# ASL1003.net
KiCad netlist of a schematic drawn in EAGLE
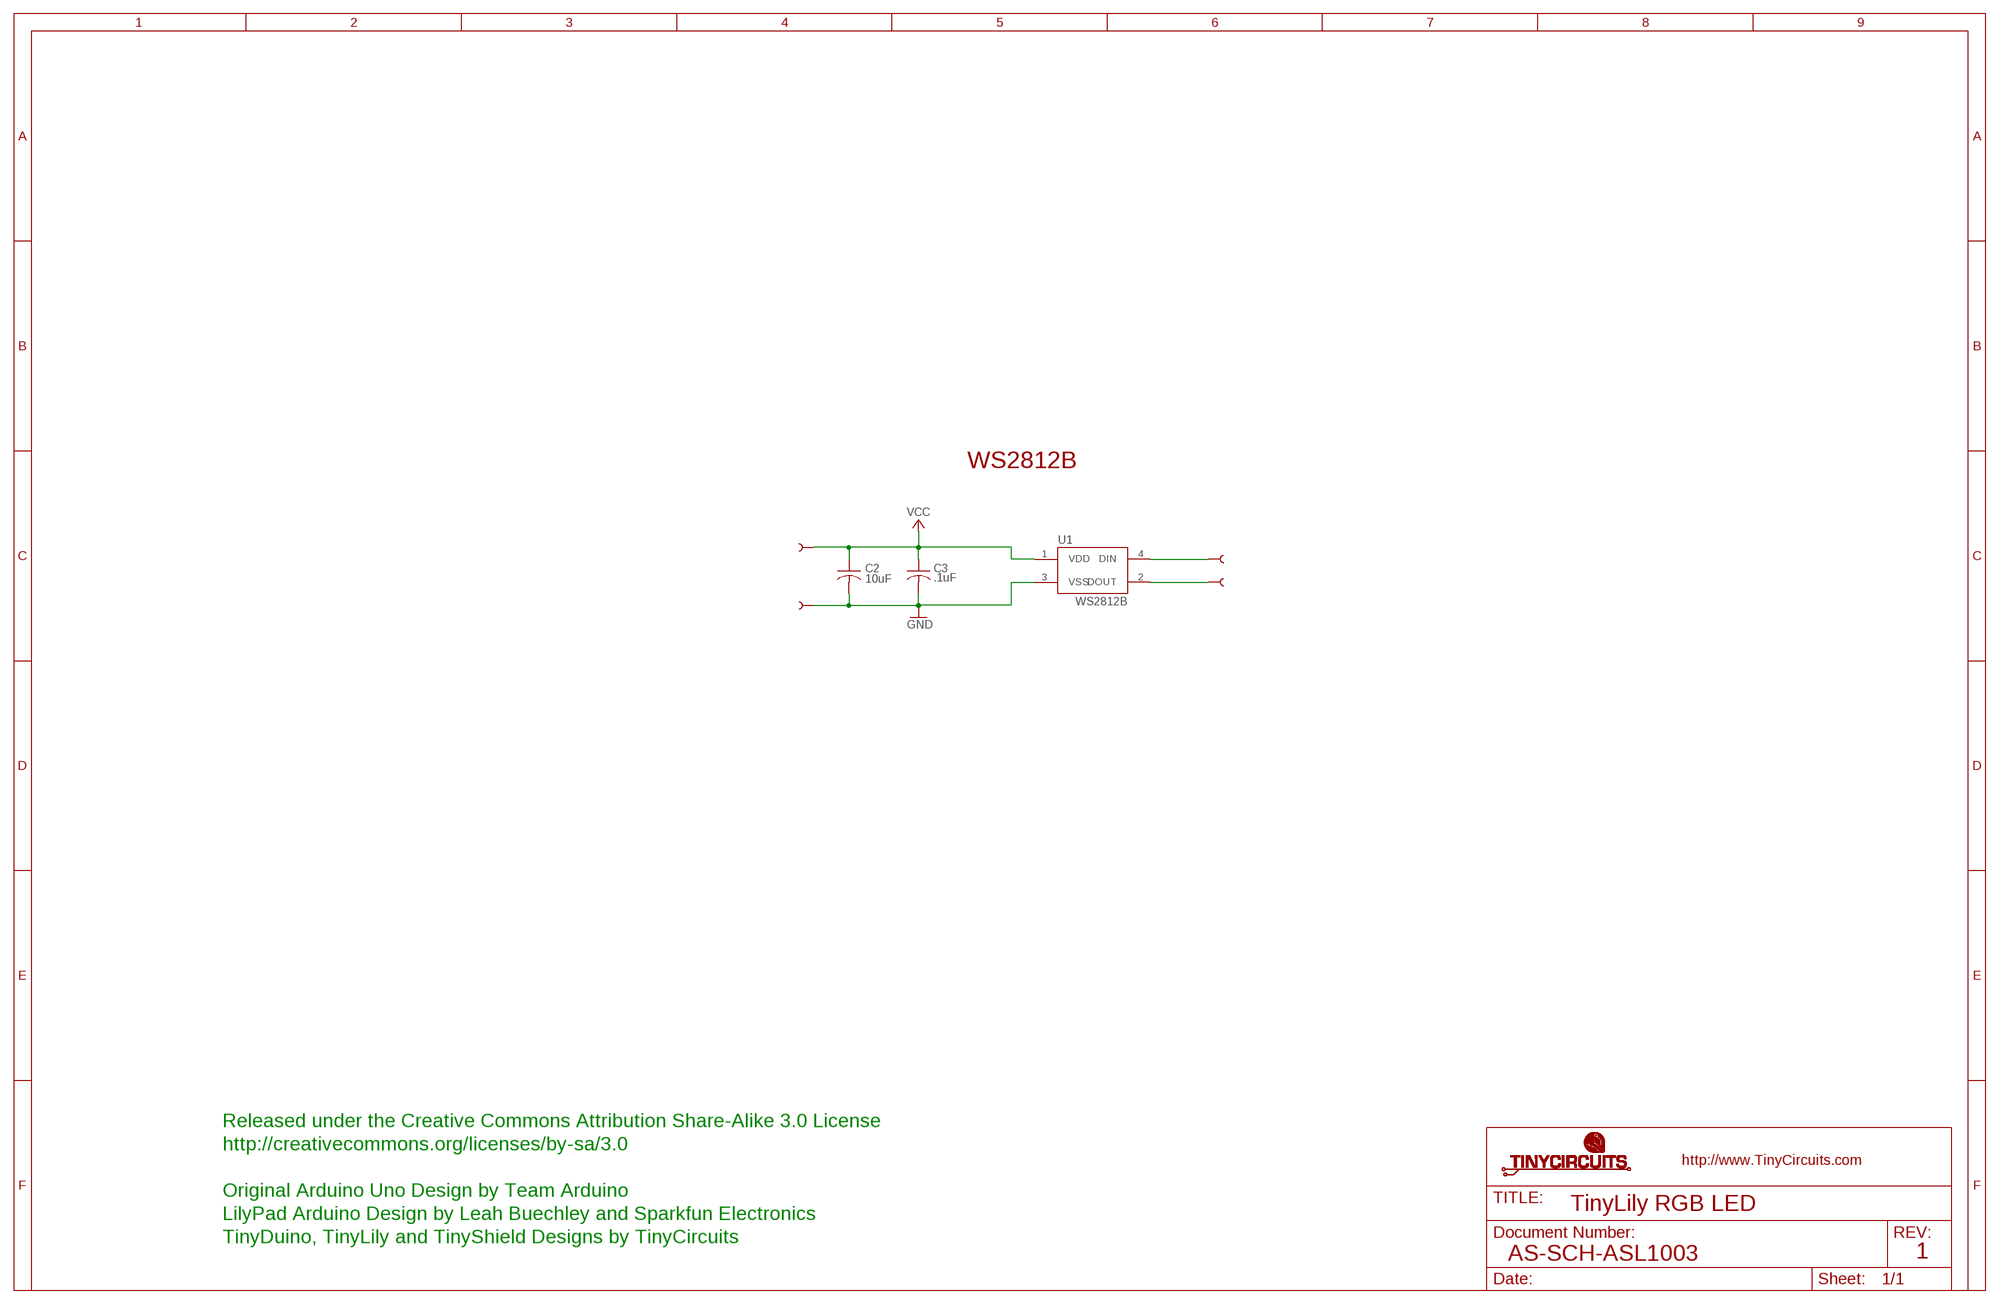
[diagram p0: schematic, sheet 1]

(export (version "E")
  (design (tool "Eeschema 10.0.6"))
  (components
    (comp (ref "C2")
      (value "10uF")
      (footprint "eagle-import:C0603")
      (fields (field (name "PARTNO") "AS-ITM-00002") (field (name "PARTNO_1") "AS-ITM-00002"))
      (libsource (lib "eagle-import") (part "AS-ITM-00002"))
    )
    (comp (ref "C3")
      (value ".1uF")
      (footprint "eagle-import:C0402")
      (fields (field (name "PARTNO") "AS-ITM-00008") (field (name "PARTNO_1") "AS-ITM-00008"))
      (libsource (lib "eagle-import") (part "AS-ITM-00008"))
    )
    (comp (ref "U$3")
      (value "SEWTABTH_10MM")
      (footprint "eagle-import:SEWTAP_TH_10MM")
      (libsource (lib "eagle-import") (part "SEWTABTH_10MM"))
    )
    (comp (ref "U$7")
      (value "SEWTABTH_10MM")
      (footprint "eagle-import:SEWTAP_TH_10MM")
      (libsource (lib "eagle-import") (part "SEWTABTH_10MM"))
    )
    (comp (ref "U$8")
      (value "SEWTABTH_10MM")
      (footprint "eagle-import:SEWTAP_TH_10MM")
      (libsource (lib "eagle-import") (part "SEWTABTH_10MM"))
    )
    (comp (ref "U$9")
      (value "SEWTABTH_10MM")
      (footprint "eagle-import:SEWTAP_TH_10MM")
      (libsource (lib "eagle-import") (part "SEWTABTH_10MM"))
    )
    (comp (ref "U1")
      (value "WS2812B")
      (footprint "eagle-import:WS2812B")
      (fields (field (name "PARTNO") "AS-ITM-00221"))
      (libsource (lib "eagle-import") (part "AS-ITM-00221"))
    )
  )
  (nets
    (net (code "1") (name "GND") (class "Default")
      (node (ref "C2") (pin "2") (pinfunction "2_2") (pintype "passive"))
      (node (ref "C3") (pin "2") (pinfunction "2_2") (pintype "passive"))
      (node (ref "U$7") (pin "1") (pinfunction "1_1") (pintype "bidirectional"))
      (node (ref "U1") (pin "3") (pinfunction "VSS_3") (pintype "bidirectional"))
    )
    (net (code "2") (name "Net-(U1-DIN)") (class "Default")
      (node (ref "U$3") (pin "1") (pinfunction "1_1") (pintype "bidirectional"))
      (node (ref "U1") (pin "4") (pinfunction "DIN_4") (pintype "bidirectional"))
    )
    (net (code "3") (name "Net-(U1-DOUT)") (class "Default")
      (node (ref "U$9") (pin "1") (pinfunction "1_1") (pintype "bidirectional"))
      (node (ref "U1") (pin "2") (pinfunction "DOUT_2") (pintype "bidirectional"))
    )
    (net (code "4") (name "VCC") (class "Default")
      (node (ref "C2") (pin "1") (pinfunction "1_1") (pintype "passive"))
      (node (ref "C3") (pin "1") (pinfunction "1_1") (pintype "passive"))
      (node (ref "U$8") (pin "1") (pinfunction "1_1") (pintype "bidirectional"))
      (node (ref "U1") (pin "1") (pinfunction "VDD_1") (pintype "bidirectional"))
    )
  )
)
